# Sheet2.net
KiCad netlist of a schematic drawn in Altium Designer
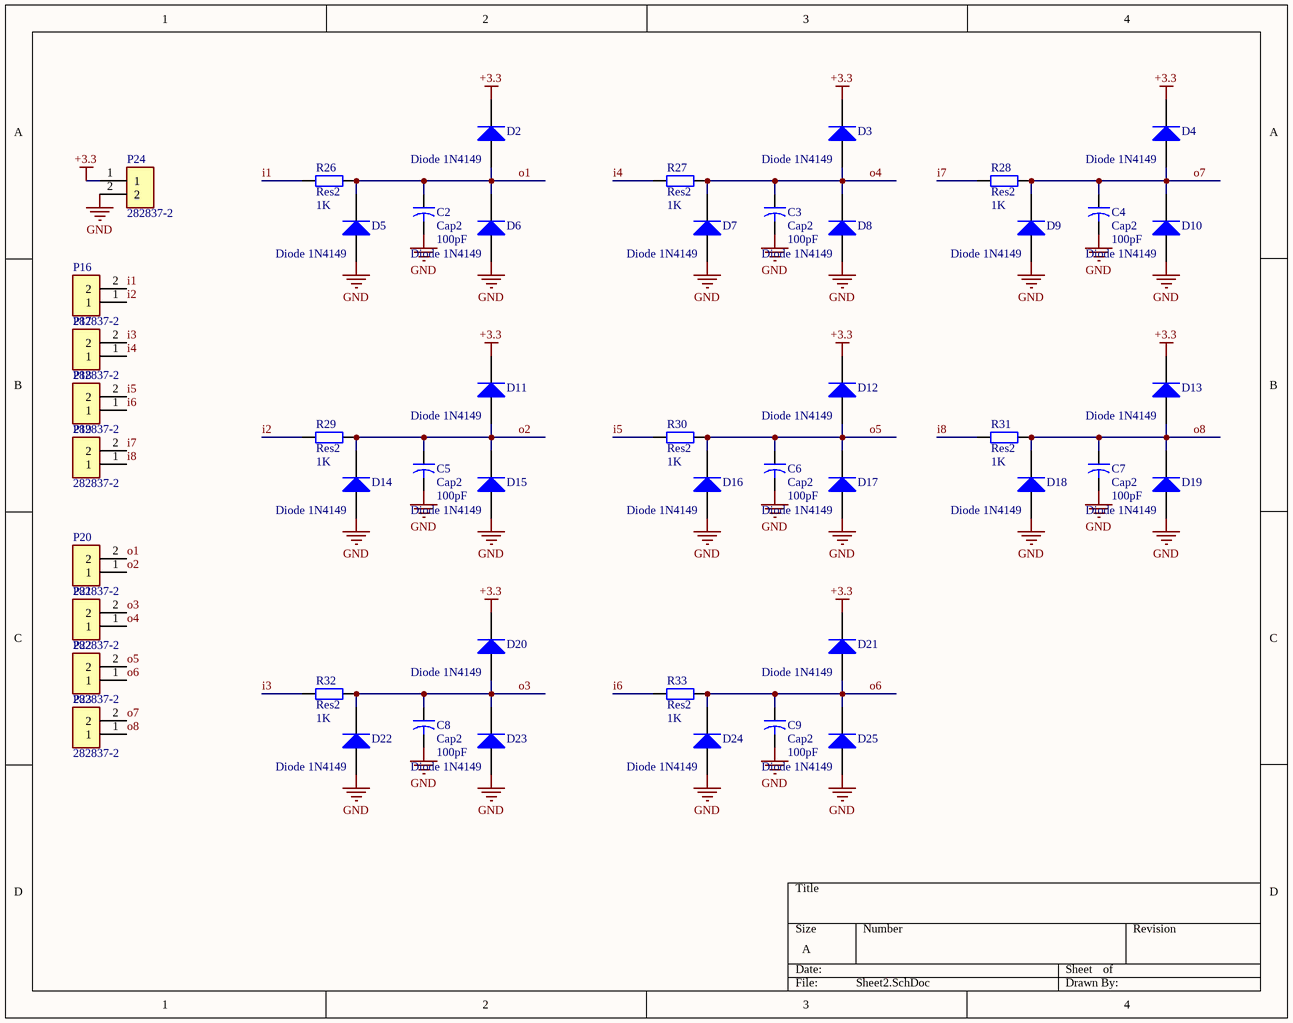
[diagram p0: Sheet2.SchDoc]

(export (version "E")
  (design (tool "Eeschema 10.0.6"))
  (components
    (comp (ref "C2")
      (value "Cap2")
      (footprint "CAPR5-4X5")
      (description "Capacitor")
      (fields (field (name "ALTIUM_VALUE") "100pF") (field (name "PUBLISHER") "Altium Limited"))
      (libsource (lib "Miscellaneous Devices") (part "Cap2"))
    )
    (comp (ref "C3")
      (value "Cap2")
      (footprint "CAPR5-4X5")
      (description "Capacitor")
      (fields (field (name "ALTIUM_VALUE") "100pF") (field (name "PUBLISHER") "Altium Limited"))
      (libsource (lib "Miscellaneous Devices") (part "Cap2"))
    )
    (comp (ref "C4")
      (value "Cap2")
      (footprint "CAPR5-4X5")
      (description "Capacitor")
      (fields (field (name "ALTIUM_VALUE") "100pF") (field (name "PUBLISHER") "Altium Limited"))
      (libsource (lib "Miscellaneous Devices") (part "Cap2"))
    )
    (comp (ref "C5")
      (value "Cap2")
      (footprint "CAPR5-4X5")
      (description "Capacitor")
      (fields (field (name "ALTIUM_VALUE") "100pF") (field (name "PUBLISHER") "Altium Limited"))
      (libsource (lib "Miscellaneous Devices") (part "Cap2"))
    )
    (comp (ref "C6")
      (value "Cap2")
      (footprint "CAPR5-4X5")
      (description "Capacitor")
      (fields (field (name "ALTIUM_VALUE") "100pF") (field (name "PUBLISHER") "Altium Limited"))
      (libsource (lib "Miscellaneous Devices") (part "Cap2"))
    )
    (comp (ref "C7")
      (value "Cap2")
      (footprint "CAPR5-4X5")
      (description "Capacitor")
      (fields (field (name "ALTIUM_VALUE") "100pF") (field (name "PUBLISHER") "Altium Limited"))
      (libsource (lib "Miscellaneous Devices") (part "Cap2"))
    )
    (comp (ref "C8")
      (value "Cap2")
      (footprint "CAPR5-4X5")
      (description "Capacitor")
      (fields (field (name "ALTIUM_VALUE") "100pF") (field (name "PUBLISHER") "Altium Limited"))
      (libsource (lib "Miscellaneous Devices") (part "Cap2"))
    )
    (comp (ref "C9")
      (value "Cap2")
      (footprint "CAPR5-4X5")
      (description "Capacitor")
      (fields (field (name "ALTIUM_VALUE") "100pF") (field (name "PUBLISHER") "Altium Limited"))
      (libsource (lib "Miscellaneous Devices") (part "Cap2"))
    )
    (comp (ref "D2")
      (value "Diode 1N4149")
      (footprint "DO-35A")
      (description "Computer Diode")
      (fields (field (name "PUBLISHER") "Altium Limited"))
      (libsource (lib "Miscellaneous Devices") (part "Diode 1N4149"))
    )
    (comp (ref "D3")
      (value "Diode 1N4149")
      (footprint "DO-35A")
      (description "Computer Diode")
      (fields (field (name "PUBLISHER") "Altium Limited"))
      (libsource (lib "Miscellaneous Devices") (part "Diode 1N4149"))
    )
    (comp (ref "D4")
      (value "Diode 1N4149")
      (footprint "DO-35A")
      (description "Computer Diode")
      (fields (field (name "PUBLISHER") "Altium Limited"))
      (libsource (lib "Miscellaneous Devices") (part "Diode 1N4149"))
    )
    (comp (ref "D5")
      (value "Diode 1N4149")
      (footprint "DO-35A")
      (description "Computer Diode")
      (fields (field (name "PUBLISHER") "Altium Limited"))
      (libsource (lib "Miscellaneous Devices") (part "Diode 1N4149"))
    )
    (comp (ref "D6")
      (value "Diode 1N4149")
      (footprint "DO-35A")
      (description "Computer Diode")
      (fields (field (name "PUBLISHER") "Altium Limited"))
      (libsource (lib "Miscellaneous Devices") (part "Diode 1N4149"))
    )
    (comp (ref "D7")
      (value "Diode 1N4149")
      (footprint "DO-35A")
      (description "Computer Diode")
      (fields (field (name "PUBLISHER") "Altium Limited"))
      (libsource (lib "Miscellaneous Devices") (part "Diode 1N4149"))
    )
    (comp (ref "D8")
      (value "Diode 1N4149")
      (footprint "DO-35A")
      (description "Computer Diode")
      (fields (field (name "PUBLISHER") "Altium Limited"))
      (libsource (lib "Miscellaneous Devices") (part "Diode 1N4149"))
    )
    (comp (ref "D9")
      (value "Diode 1N4149")
      (footprint "DO-35A")
      (description "Computer Diode")
      (fields (field (name "PUBLISHER") "Altium Limited"))
      (libsource (lib "Miscellaneous Devices") (part "Diode 1N4149"))
    )
    (comp (ref "D10")
      (value "Diode 1N4149")
      (footprint "DO-35A")
      (description "Computer Diode")
      (fields (field (name "PUBLISHER") "Altium Limited"))
      (libsource (lib "Miscellaneous Devices") (part "Diode 1N4149"))
    )
    (comp (ref "D11")
      (value "Diode 1N4149")
      (footprint "DO-35A")
      (description "Computer Diode")
      (fields (field (name "PUBLISHER") "Altium Limited"))
      (libsource (lib "Miscellaneous Devices") (part "Diode 1N4149"))
    )
    (comp (ref "D12")
      (value "Diode 1N4149")
      (footprint "DO-35A")
      (description "Computer Diode")
      (fields (field (name "PUBLISHER") "Altium Limited"))
      (libsource (lib "Miscellaneous Devices") (part "Diode 1N4149"))
    )
    (comp (ref "D13")
      (value "Diode 1N4149")
      (footprint "DO-35A")
      (description "Computer Diode")
      (fields (field (name "PUBLISHER") "Altium Limited"))
      (libsource (lib "Miscellaneous Devices") (part "Diode 1N4149"))
    )
    (comp (ref "D14")
      (value "Diode 1N4149")
      (footprint "DO-35A")
      (description "Computer Diode")
      (fields (field (name "PUBLISHER") "Altium Limited"))
      (libsource (lib "Miscellaneous Devices") (part "Diode 1N4149"))
    )
    (comp (ref "D15")
      (value "Diode 1N4149")
      (footprint "DO-35A")
      (description "Computer Diode")
      (fields (field (name "PUBLISHER") "Altium Limited"))
      (libsource (lib "Miscellaneous Devices") (part "Diode 1N4149"))
    )
    (comp (ref "D16")
      (value "Diode 1N4149")
      (footprint "DO-35A")
      (description "Computer Diode")
      (fields (field (name "PUBLISHER") "Altium Limited"))
      (libsource (lib "Miscellaneous Devices") (part "Diode 1N4149"))
    )
    (comp (ref "D17")
      (value "Diode 1N4149")
      (footprint "DO-35A")
      (description "Computer Diode")
      (fields (field (name "PUBLISHER") "Altium Limited"))
      (libsource (lib "Miscellaneous Devices") (part "Diode 1N4149"))
    )
    (comp (ref "D18")
      (value "Diode 1N4149")
      (footprint "DO-35A")
      (description "Computer Diode")
      (fields (field (name "PUBLISHER") "Altium Limited"))
      (libsource (lib "Miscellaneous Devices") (part "Diode 1N4149"))
    )
    (comp (ref "D19")
      (value "Diode 1N4149")
      (footprint "DO-35A")
      (description "Computer Diode")
      (fields (field (name "PUBLISHER") "Altium Limited"))
      (libsource (lib "Miscellaneous Devices") (part "Diode 1N4149"))
    )
    (comp (ref "D20")
      (value "Diode 1N4149")
      (footprint "DO-35A")
      (description "Computer Diode")
      (fields (field (name "PUBLISHER") "Altium Limited"))
      (libsource (lib "Miscellaneous Devices") (part "Diode 1N4149"))
    )
    (comp (ref "D21")
      (value "Diode 1N4149")
      (footprint "DO-35A")
      (description "Computer Diode")
      (fields (field (name "PUBLISHER") "Altium Limited"))
      (libsource (lib "Miscellaneous Devices") (part "Diode 1N4149"))
    )
    (comp (ref "D22")
      (value "Diode 1N4149")
      (footprint "DO-35A")
      (description "Computer Diode")
      (fields (field (name "PUBLISHER") "Altium Limited"))
      (libsource (lib "Miscellaneous Devices") (part "Diode 1N4149"))
    )
    (comp (ref "D23")
      (value "Diode 1N4149")
      (footprint "DO-35A")
      (description "Computer Diode")
      (fields (field (name "PUBLISHER") "Altium Limited"))
      (libsource (lib "Miscellaneous Devices") (part "Diode 1N4149"))
    )
    (comp (ref "D24")
      (value "Diode 1N4149")
      (footprint "DO-35A")
      (description "Computer Diode")
      (fields (field (name "PUBLISHER") "Altium Limited"))
      (libsource (lib "Miscellaneous Devices") (part "Diode 1N4149"))
    )
    (comp (ref "D25")
      (value "Diode 1N4149")
      (footprint "DO-35A")
      (description "Computer Diode")
      (fields (field (name "PUBLISHER") "Altium Limited"))
      (libsource (lib "Miscellaneous Devices") (part "Diode 1N4149"))
    )
    (comp (ref "P16")
      (value "282837-2")
      (footprint "TE_282837-2")
      (fields (field (name "MF") "TE Connectivity"))
      (libsource (lib "") (part "282837-2_1"))
    )
    (comp (ref "P17")
      (value "282837-2")
      (footprint "TE_282837-2")
      (fields (field (name "MF") "TE Connectivity"))
      (libsource (lib "") (part "282837-2_1"))
    )
    (comp (ref "P18")
      (value "282837-2")
      (footprint "TE_282837-2")
      (fields (field (name "MF") "TE Connectivity"))
      (libsource (lib "") (part "282837-2_1"))
    )
    (comp (ref "P19")
      (value "282837-2")
      (footprint "TE_282837-2")
      (fields (field (name "MF") "TE Connectivity"))
      (libsource (lib "") (part "282837-2_1"))
    )
    (comp (ref "P20")
      (value "282837-2")
      (footprint "TE_282837-2")
      (fields (field (name "MF") "TE Connectivity"))
      (libsource (lib "") (part "282837-2_1"))
    )
    (comp (ref "P21")
      (value "282837-2")
      (footprint "TE_282837-2")
      (fields (field (name "MF") "TE Connectivity"))
      (libsource (lib "") (part "282837-2_1"))
    )
    (comp (ref "P22")
      (value "282837-2")
      (footprint "TE_282837-2")
      (fields (field (name "MF") "TE Connectivity"))
      (libsource (lib "") (part "282837-2_1"))
    )
    (comp (ref "P23")
      (value "282837-2")
      (footprint "TE_282837-2")
      (fields (field (name "MF") "TE Connectivity"))
      (libsource (lib "") (part "282837-2_1"))
    )
    (comp (ref "P24")
      (value "282837-2")
      (footprint "TE_282837-2")
      (fields (field (name "MF") "TE Connectivity"))
      (libsource (lib "282837-2") (part "282837-2"))
    )
    (comp (ref "R26")
      (value "Res2")
      (footprint "AXIAL-0.4")
      (description "Resistor")
      (fields (field (name "ALTIUM_VALUE") "1K") (field (name "PUBLISHER") "Altium Limited"))
      (libsource (lib "Miscellaneous Devices") (part "Res2"))
    )
    (comp (ref "R27")
      (value "Res2")
      (footprint "AXIAL-0.4")
      (description "Resistor")
      (fields (field (name "ALTIUM_VALUE") "1K") (field (name "PUBLISHER") "Altium Limited"))
      (libsource (lib "Miscellaneous Devices") (part "Res2"))
    )
    (comp (ref "R28")
      (value "Res2")
      (footprint "AXIAL-0.4")
      (description "Resistor")
      (fields (field (name "ALTIUM_VALUE") "1K") (field (name "PUBLISHER") "Altium Limited"))
      (libsource (lib "Miscellaneous Devices") (part "Res2"))
    )
    (comp (ref "R29")
      (value "Res2")
      (footprint "AXIAL-0.4")
      (description "Resistor")
      (fields (field (name "ALTIUM_VALUE") "1K") (field (name "PUBLISHER") "Altium Limited"))
      (libsource (lib "Miscellaneous Devices") (part "Res2"))
    )
    (comp (ref "R30")
      (value "Res2")
      (footprint "AXIAL-0.4")
      (description "Resistor")
      (fields (field (name "ALTIUM_VALUE") "1K") (field (name "PUBLISHER") "Altium Limited"))
      (libsource (lib "Miscellaneous Devices") (part "Res2"))
    )
    (comp (ref "R31")
      (value "Res2")
      (footprint "AXIAL-0.4")
      (description "Resistor")
      (fields (field (name "ALTIUM_VALUE") "1K") (field (name "PUBLISHER") "Altium Limited"))
      (libsource (lib "Miscellaneous Devices") (part "Res2"))
    )
    (comp (ref "R32")
      (value "Res2")
      (footprint "AXIAL-0.4")
      (description "Resistor")
      (fields (field (name "ALTIUM_VALUE") "1K") (field (name "PUBLISHER") "Altium Limited"))
      (libsource (lib "Miscellaneous Devices") (part "Res2"))
    )
    (comp (ref "R33")
      (value "Res2")
      (footprint "AXIAL-0.4")
      (description "Resistor")
      (fields (field (name "ALTIUM_VALUE") "1K") (field (name "PUBLISHER") "Altium Limited"))
      (libsource (lib "Miscellaneous Devices") (part "Res2"))
    )
  )
  (nets
    (net (code "1") (name "+3.3") (class "Default")
      (node (ref "D11") (pin "2") (pinfunction "K_2") (pintype "passive"))
      (node (ref "D12") (pin "2") (pinfunction "K_2") (pintype "passive"))
      (node (ref "D13") (pin "2") (pinfunction "K_2") (pintype "passive"))
      (node (ref "D2") (pin "2") (pinfunction "K_2") (pintype "passive"))
      (node (ref "D20") (pin "2") (pinfunction "K_2") (pintype "passive"))
      (node (ref "D21") (pin "2") (pinfunction "K_2") (pintype "passive"))
      (node (ref "D3") (pin "2") (pinfunction "K_2") (pintype "passive"))
      (node (ref "D4") (pin "2") (pinfunction "K_2") (pintype "passive"))
      (node (ref "P24") (pin "1") (pinfunction "1_1") (pintype "passive"))
    )
    (net (code "2") (name "/i1") (class "Default")
      (node (ref "P16") (pin "2") (pinfunction "2_2") (pintype "passive"))
      (node (ref "R26") (pin "2") (pinfunction "2_2") (pintype "passive"))
    )
    (net (code "3") (name "/i2") (class "Default")
      (node (ref "P16") (pin "1") (pinfunction "1_1") (pintype "passive"))
      (node (ref "R29") (pin "2") (pinfunction "2_2") (pintype "passive"))
    )
    (net (code "4") (name "/i3") (class "Default")
      (node (ref "P17") (pin "2") (pinfunction "2_2") (pintype "passive"))
      (node (ref "R32") (pin "2") (pinfunction "2_2") (pintype "passive"))
    )
    (net (code "5") (name "/i4") (class "Default")
      (node (ref "P17") (pin "1") (pinfunction "1_1") (pintype "passive"))
      (node (ref "R27") (pin "2") (pinfunction "2_2") (pintype "passive"))
    )
    (net (code "6") (name "/i5") (class "Default")
      (node (ref "P18") (pin "2") (pinfunction "2_2") (pintype "passive"))
      (node (ref "R30") (pin "2") (pinfunction "2_2") (pintype "passive"))
    )
    (net (code "7") (name "/i6") (class "Default")
      (node (ref "P18") (pin "1") (pinfunction "1_1") (pintype "passive"))
      (node (ref "R33") (pin "2") (pinfunction "2_2") (pintype "passive"))
    )
    (net (code "8") (name "/i7") (class "Default")
      (node (ref "P19") (pin "2") (pinfunction "2_2") (pintype "passive"))
      (node (ref "R28") (pin "2") (pinfunction "2_2") (pintype "passive"))
    )
    (net (code "9") (name "/i8") (class "Default")
      (node (ref "P19") (pin "1") (pinfunction "1_1") (pintype "passive"))
      (node (ref "R31") (pin "2") (pinfunction "2_2") (pintype "passive"))
    )
    (net (code "10") (name "/o1") (class "Default")
      (node (ref "C2") (pin "1") (pinfunction "1_1") (pintype "passive"))
      (node (ref "D2") (pin "1") (pinfunction "A_1") (pintype "passive"))
      (node (ref "D5") (pin "2") (pinfunction "K_2") (pintype "passive"))
      (node (ref "D6") (pin "2") (pinfunction "K_2") (pintype "passive"))
      (node (ref "P20") (pin "2") (pinfunction "2_2") (pintype "passive"))
      (node (ref "R26") (pin "1") (pinfunction "1_1") (pintype "passive"))
    )
    (net (code "11") (name "/o2") (class "Default")
      (node (ref "C5") (pin "1") (pinfunction "1_1") (pintype "passive"))
      (node (ref "D11") (pin "1") (pinfunction "A_1") (pintype "passive"))
      (node (ref "D14") (pin "2") (pinfunction "K_2") (pintype "passive"))
      (node (ref "D15") (pin "2") (pinfunction "K_2") (pintype "passive"))
      (node (ref "P20") (pin "1") (pinfunction "1_1") (pintype "passive"))
      (node (ref "R29") (pin "1") (pinfunction "1_1") (pintype "passive"))
    )
    (net (code "12") (name "/o3") (class "Default")
      (node (ref "C8") (pin "1") (pinfunction "1_1") (pintype "passive"))
      (node (ref "D20") (pin "1") (pinfunction "A_1") (pintype "passive"))
      (node (ref "D22") (pin "2") (pinfunction "K_2") (pintype "passive"))
      (node (ref "D23") (pin "2") (pinfunction "K_2") (pintype "passive"))
      (node (ref "P21") (pin "2") (pinfunction "2_2") (pintype "passive"))
      (node (ref "R32") (pin "1") (pinfunction "1_1") (pintype "passive"))
    )
    (net (code "13") (name "/o4") (class "Default")
      (node (ref "C3") (pin "1") (pinfunction "1_1") (pintype "passive"))
      (node (ref "D3") (pin "1") (pinfunction "A_1") (pintype "passive"))
      (node (ref "D7") (pin "2") (pinfunction "K_2") (pintype "passive"))
      (node (ref "D8") (pin "2") (pinfunction "K_2") (pintype "passive"))
      (node (ref "P21") (pin "1") (pinfunction "1_1") (pintype "passive"))
      (node (ref "R27") (pin "1") (pinfunction "1_1") (pintype "passive"))
    )
    (net (code "14") (name "/o5") (class "Default")
      (node (ref "C6") (pin "1") (pinfunction "1_1") (pintype "passive"))
      (node (ref "D12") (pin "1") (pinfunction "A_1") (pintype "passive"))
      (node (ref "D16") (pin "2") (pinfunction "K_2") (pintype "passive"))
      (node (ref "D17") (pin "2") (pinfunction "K_2") (pintype "passive"))
      (node (ref "P22") (pin "2") (pinfunction "2_2") (pintype "passive"))
      (node (ref "R30") (pin "1") (pinfunction "1_1") (pintype "passive"))
    )
    (net (code "15") (name "/o6") (class "Default")
      (node (ref "C9") (pin "1") (pinfunction "1_1") (pintype "passive"))
      (node (ref "D21") (pin "1") (pinfunction "A_1") (pintype "passive"))
      (node (ref "D24") (pin "2") (pinfunction "K_2") (pintype "passive"))
      (node (ref "D25") (pin "2") (pinfunction "K_2") (pintype "passive"))
      (node (ref "P22") (pin "1") (pinfunction "1_1") (pintype "passive"))
      (node (ref "R33") (pin "1") (pinfunction "1_1") (pintype "passive"))
    )
    (net (code "16") (name "/o7") (class "Default")
      (node (ref "C4") (pin "1") (pinfunction "1_1") (pintype "passive"))
      (node (ref "D10") (pin "2") (pinfunction "K_2") (pintype "passive"))
      (node (ref "D4") (pin "1") (pinfunction "A_1") (pintype "passive"))
      (node (ref "D9") (pin "2") (pinfunction "K_2") (pintype "passive"))
      (node (ref "P23") (pin "2") (pinfunction "2_2") (pintype "passive"))
      (node (ref "R28") (pin "1") (pinfunction "1_1") (pintype "passive"))
    )
    (net (code "17") (name "/o8") (class "Default")
      (node (ref "C7") (pin "1") (pinfunction "1_1") (pintype "passive"))
      (node (ref "D13") (pin "1") (pinfunction "A_1") (pintype "passive"))
      (node (ref "D18") (pin "2") (pinfunction "K_2") (pintype "passive"))
      (node (ref "D19") (pin "2") (pinfunction "K_2") (pintype "passive"))
      (node (ref "P23") (pin "1") (pinfunction "1_1") (pintype "passive"))
      (node (ref "R31") (pin "1") (pinfunction "1_1") (pintype "passive"))
    )
    (net (code "18") (name "GND") (class "Default")
      (node (ref "C2") (pin "2") (pinfunction "2_2") (pintype "passive"))
      (node (ref "C3") (pin "2") (pinfunction "2_2") (pintype "passive"))
      (node (ref "C4") (pin "2") (pinfunction "2_2") (pintype "passive"))
      (node (ref "C5") (pin "2") (pinfunction "2_2") (pintype "passive"))
      (node (ref "C6") (pin "2") (pinfunction "2_2") (pintype "passive"))
      (node (ref "C7") (pin "2") (pinfunction "2_2") (pintype "passive"))
      (node (ref "C8") (pin "2") (pinfunction "2_2") (pintype "passive"))
      (node (ref "C9") (pin "2") (pinfunction "2_2") (pintype "passive"))
      (node (ref "D10") (pin "1") (pinfunction "A_1") (pintype "passive"))
      (node (ref "D14") (pin "1") (pinfunction "A_1") (pintype "passive"))
      (node (ref "D15") (pin "1") (pinfunction "A_1") (pintype "passive"))
      (node (ref "D16") (pin "1") (pinfunction "A_1") (pintype "passive"))
      (node (ref "D17") (pin "1") (pinfunction "A_1") (pintype "passive"))
      (node (ref "D18") (pin "1") (pinfunction "A_1") (pintype "passive"))
      (node (ref "D19") (pin "1") (pinfunction "A_1") (pintype "passive"))
      (node (ref "D22") (pin "1") (pinfunction "A_1") (pintype "passive"))
      (node (ref "D23") (pin "1") (pinfunction "A_1") (pintype "passive"))
      (node (ref "D24") (pin "1") (pinfunction "A_1") (pintype "passive"))
      (node (ref "D25") (pin "1") (pinfunction "A_1") (pintype "passive"))
      (node (ref "D5") (pin "1") (pinfunction "A_1") (pintype "passive"))
      (node (ref "D6") (pin "1") (pinfunction "A_1") (pintype "passive"))
      (node (ref "D7") (pin "1") (pinfunction "A_1") (pintype "passive"))
      (node (ref "D8") (pin "1") (pinfunction "A_1") (pintype "passive"))
      (node (ref "D9") (pin "1") (pinfunction "A_1") (pintype "passive"))
      (node (ref "P24") (pin "2") (pinfunction "2_2") (pintype "passive"))
    )
  )
)
